# MBC5_1-3.net
KiCad netlist of a schematic drawn in EAGLE
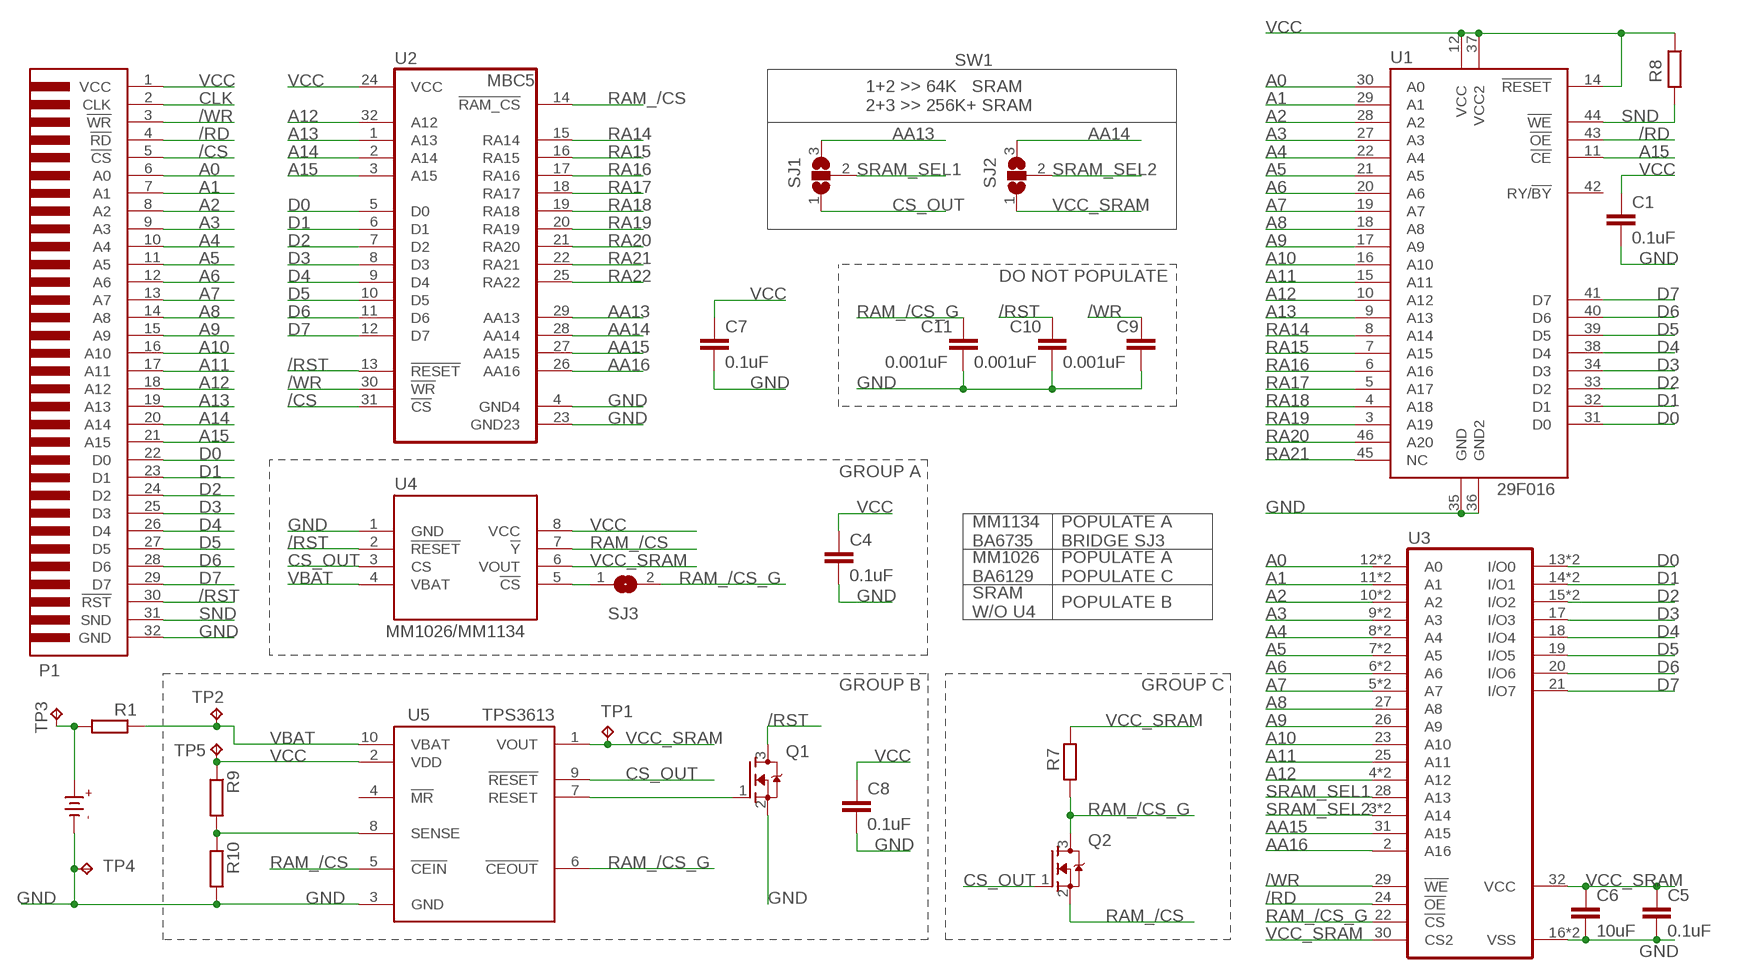
[diagram p0: schematic, sheet 1]

(export (version "E")
  (design (tool "Eeschema 10.0.6"))
  (components
    (comp (ref "B1")
      (value "CR2025")
      (footprint "eagle-import:CR2025")
      (libsource (lib "eagle-import") (part "CR2025"))
    )
    (comp (ref "C1")
      (value "0.1uF")
      (footprint "eagle-import:C0603")
      (libsource (lib "eagle-import") (part "C-EUC0603"))
    )
    (comp (ref "C4")
      (value "0.1uF")
      (footprint "eagle-import:C0603")
      (libsource (lib "eagle-import") (part "C-EUC0603"))
    )
    (comp (ref "C5")
      (value "0.1uF")
      (footprint "eagle-import:C0603")
      (libsource (lib "eagle-import") (part "C-EUC0603"))
    )
    (comp (ref "C6")
      (value "10uF")
      (footprint "eagle-import:C0603")
      (libsource (lib "eagle-import") (part "C-EUC0603"))
    )
    (comp (ref "C7")
      (value "0.1uF")
      (footprint "eagle-import:C0603")
      (libsource (lib "eagle-import") (part "C-EUC0603"))
    )
    (comp (ref "C8")
      (value "0.1uF")
      (footprint "eagle-import:C0603")
      (libsource (lib "eagle-import") (part "C-EUC0603"))
    )
    (comp (ref "C9")
      (value "0.001uF")
      (footprint "eagle-import:C0603")
      (libsource (lib "eagle-import") (part "C-EUC0603"))
    )
    (comp (ref "C10")
      (value "0.001uF")
      (footprint "eagle-import:C0603")
      (libsource (lib "eagle-import") (part "C-EUC0603"))
    )
    (comp (ref "C11")
      (value "0.001uF")
      (footprint "eagle-import:C0603")
      (libsource (lib "eagle-import") (part "C-EUC0603"))
    )
    (comp (ref "P1")
      (value "GBC_CART")
      (footprint "eagle-import:GBC_CART")
      (libsource (lib "eagle-import") (part "GBC_CART"))
    )
    (comp (ref "Q1")
      (value "2N7002")
      (footprint "eagle-import:SOT23")
      (libsource (lib "eagle-import") (part "MOSFET-NREFLOW"))
    )
    (comp (ref "Q2")
      (value "2N7002")
      (footprint "eagle-import:SOT23")
      (libsource (lib "eagle-import") (part "MOSFET-NREFLOW"))
    )
    (comp (ref "R1")
      (value "RR0603")
      (footprint "eagle-import:R0603")
      (libsource (lib "eagle-import") (part "RR0603"))
    )
    (comp (ref "R7")
      (value "RR0603")
      (footprint "eagle-import:R0603")
      (libsource (lib "eagle-import") (part "RR0603"))
    )
    (comp (ref "R8")
      (value "RR0603")
      (footprint "eagle-import:R0603")
      (libsource (lib "eagle-import") (part "RR0603"))
    )
    (comp (ref "R9")
      (value "RR0603")
      (footprint "eagle-import:R0603")
      (libsource (lib "eagle-import") (part "RR0603"))
    )
    (comp (ref "R10")
      (value "RR0603")
      (footprint "eagle-import:R0603")
      (libsource (lib "eagle-import") (part "RR0603"))
    )
    (comp (ref "SJ1")
      (value "SJ2W")
      (footprint "eagle-import:SJ_2")
      (libsource (lib "eagle-import") (part "SJ2W"))
    )
    (comp (ref "SJ2")
      (value "SJ2W")
      (footprint "eagle-import:SJ_2")
      (libsource (lib "eagle-import") (part "SJ2W"))
    )
    (comp (ref "SJ3") (value "SJ") (footprint "eagle-import:SJ") (libsource (lib "eagle-import") (part "SJ")))
    (comp (ref "TP1")
      (value "TPB1,27")
      (footprint "eagle-import:B1,27")
      (libsource (lib "eagle-import") (part "TPB1,27"))
    )
    (comp (ref "TP2")
      (value "TPB1,27")
      (footprint "eagle-import:B1,27")
      (libsource (lib "eagle-import") (part "TPB1,27"))
    )
    (comp (ref "TP3")
      (value "TPB1,27")
      (footprint "eagle-import:B1,27")
      (libsource (lib "eagle-import") (part "TPB1,27"))
    )
    (comp (ref "TP4")
      (value "TPB1,27")
      (footprint "eagle-import:B1,27")
      (libsource (lib "eagle-import") (part "TPB1,27"))
    )
    (comp (ref "TP5")
      (value "TPB1,27")
      (footprint "eagle-import:B1,27")
      (libsource (lib "eagle-import") (part "TPB1,27"))
    )
    (comp (ref "U1")
      (value "29F016")
      (footprint "eagle-import:TSOP-48")
      (libsource (lib "eagle-import") (part "29F016"))
    )
    (comp (ref "U2")
      (value "MBC5")
      (footprint "eagle-import:QFP-32")
      (libsource (lib "eagle-import") (part "MBC5"))
    )
    (comp (ref "U3")
      (value "1008L")
      (footprint "eagle-import:SO32L_L")
      (libsource (lib "eagle-import") (part "1008L"))
    )
    (comp (ref "U4")
      (value "MM1134")
      (footprint "eagle-import:SOIC-8")
      (libsource (lib "eagle-import") (part "MM1134"))
    )
    (comp (ref "U5")
      (value "TPS3613")
      (footprint "eagle-import:MSOP-10")
      (libsource (lib "eagle-import") (part "TPS3613"))
    )
  )
  (nets
    (net (code "1") (name "/A0") (class "Default")
      (node (ref "P1") (pin "6") (pinfunction "A0_6") (pintype "output"))
      (node (ref "U1") (pin "30") (pinfunction "A0_30") (pintype "input"))
      (node (ref "U3") (pin "12") (pinfunction "A0_12") (pintype "input"))
      (node (ref "U3") (pin "L12") (pinfunction "A0_L12") (pintype "input"))
    )
    (net (code "2") (name "/A1") (class "Default")
      (node (ref "P1") (pin "7") (pinfunction "A1_7") (pintype "output"))
      (node (ref "U1") (pin "29") (pinfunction "A1_29") (pintype "input"))
      (node (ref "U3") (pin "11") (pinfunction "A1_11") (pintype "input"))
      (node (ref "U3") (pin "L11") (pinfunction "A1_L11") (pintype "input"))
    )
    (net (code "3") (name "/A2") (class "Default")
      (node (ref "P1") (pin "8") (pinfunction "A2_8") (pintype "output"))
      (node (ref "U1") (pin "28") (pinfunction "A2_28") (pintype "input"))
      (node (ref "U3") (pin "10") (pinfunction "A2_10") (pintype "input"))
      (node (ref "U3") (pin "L10") (pinfunction "A2_L10") (pintype "input"))
    )
    (net (code "4") (name "/A3") (class "Default")
      (node (ref "P1") (pin "9") (pinfunction "A3_9") (pintype "output"))
      (node (ref "U1") (pin "27") (pinfunction "A3_27") (pintype "input"))
      (node (ref "U3") (pin "9") (pinfunction "A3_9") (pintype "input"))
      (node (ref "U3") (pin "L9") (pinfunction "A3_L9") (pintype "input"))
    )
    (net (code "5") (name "/A4") (class "Default")
      (node (ref "P1") (pin "10") (pinfunction "A4_10") (pintype "output"))
      (node (ref "U1") (pin "22") (pinfunction "A4_22") (pintype "input"))
      (node (ref "U3") (pin "8") (pinfunction "A4_8") (pintype "input"))
      (node (ref "U3") (pin "L8") (pinfunction "A4_L8") (pintype "input"))
    )
    (net (code "6") (name "/A5") (class "Default")
      (node (ref "P1") (pin "11") (pinfunction "A5_11") (pintype "output"))
      (node (ref "U1") (pin "21") (pinfunction "A5_21") (pintype "input"))
      (node (ref "U3") (pin "7") (pinfunction "A5_7") (pintype "input"))
      (node (ref "U3") (pin "L7") (pinfunction "A5_L7") (pintype "input"))
    )
    (net (code "7") (name "/A6") (class "Default")
      (node (ref "P1") (pin "12") (pinfunction "A6_12") (pintype "output"))
      (node (ref "U1") (pin "20") (pinfunction "A6_20") (pintype "input"))
      (node (ref "U3") (pin "6") (pinfunction "A6_6") (pintype "input"))
      (node (ref "U3") (pin "L6") (pinfunction "A6_L6") (pintype "input"))
    )
    (net (code "8") (name "/A7") (class "Default")
      (node (ref "P1") (pin "13") (pinfunction "A7_13") (pintype "output"))
      (node (ref "U1") (pin "19") (pinfunction "A7_19") (pintype "input"))
      (node (ref "U3") (pin "5") (pinfunction "A7_5") (pintype "input"))
      (node (ref "U3") (pin "L5") (pinfunction "A7_L5") (pintype "input"))
    )
    (net (code "9") (name "/A8") (class "Default")
      (node (ref "P1") (pin "14") (pinfunction "A8_14") (pintype "output"))
      (node (ref "U1") (pin "18") (pinfunction "A8_18") (pintype "input"))
      (node (ref "U3") (pin "27") (pinfunction "A8_27") (pintype "input"))
    )
    (net (code "10") (name "/A9") (class "Default")
      (node (ref "P1") (pin "15") (pinfunction "A9_15") (pintype "output"))
      (node (ref "U1") (pin "17") (pinfunction "A9_17") (pintype "input"))
      (node (ref "U3") (pin "26") (pinfunction "A9_26") (pintype "input"))
    )
    (net (code "11") (name "/A10") (class "Default")
      (node (ref "P1") (pin "16") (pinfunction "A10_16") (pintype "output"))
      (node (ref "U1") (pin "16") (pinfunction "A10_16") (pintype "input"))
      (node (ref "U3") (pin "23") (pinfunction "A10_23") (pintype "input"))
    )
    (net (code "12") (name "/A11") (class "Default")
      (node (ref "P1") (pin "17") (pinfunction "A11_17") (pintype "output"))
      (node (ref "U1") (pin "15") (pinfunction "A11_15") (pintype "input"))
      (node (ref "U3") (pin "25") (pinfunction "A11_25") (pintype "input"))
    )
    (net (code "13") (name "/A12") (class "Default")
      (node (ref "P1") (pin "18") (pinfunction "A12_18") (pintype "output"))
      (node (ref "U1") (pin "10") (pinfunction "A12_10") (pintype "input"))
      (node (ref "U2") (pin "32") (pinfunction "A12_32") (pintype "input"))
      (node (ref "U3") (pin "4") (pinfunction "A12_4") (pintype "input"))
      (node (ref "U3") (pin "L4") (pinfunction "A12_L4") (pintype "input"))
    )
    (net (code "14") (name "/A13") (class "Default")
      (node (ref "P1") (pin "19") (pinfunction "A13_19") (pintype "output"))
      (node (ref "U1") (pin "9") (pinfunction "A13_9") (pintype "input"))
      (node (ref "U2") (pin "1") (pinfunction "A13_1") (pintype "input"))
    )
    (net (code "15") (name "/A14") (class "Default")
      (node (ref "P1") (pin "20") (pinfunction "A14_20") (pintype "output"))
      (node (ref "U2") (pin "2") (pinfunction "A14_2") (pintype "input"))
    )
    (net (code "16") (name "/A15") (class "Default")
      (node (ref "P1") (pin "21") (pinfunction "A15_21") (pintype "output"))
      (node (ref "U1") (pin "11") (pinfunction "~{CE}_11") (pintype "input"))
      (node (ref "U2") (pin "3") (pinfunction "A15_3") (pintype "input"))
    )
    (net (code "17") (name "/AA13") (class "Default")
      (node (ref "SJ1") (pin "3") (pinfunction "3_3") (pintype "passive"))
      (node (ref "U2") (pin "29") (pinfunction "AA13_29") (pintype "output"))
    )
    (net (code "18") (name "/AA14") (class "Default")
      (node (ref "SJ2") (pin "3") (pinfunction "3_3") (pintype "passive"))
      (node (ref "U2") (pin "28") (pinfunction "AA14_28") (pintype "output"))
    )
    (net (code "19") (name "/AA15") (class "Default")
      (node (ref "U2") (pin "27") (pinfunction "AA15_27") (pintype "output"))
      (node (ref "U3") (pin "31") (pinfunction "A15_31") (pintype "input"))
    )
    (net (code "20") (name "/AA16") (class "Default")
      (node (ref "U2") (pin "26") (pinfunction "AA16_26") (pintype "output"))
      (node (ref "U3") (pin "2") (pinfunction "A16_2") (pintype "input"))
    )
    (net (code "21") (name "/CLK") (class "Default")
      (node (ref "P1") (pin "2") (pinfunction "CLK_2") (pintype "output"))
    )
    (net (code "22") (name "/CS_OUT") (class "Default")
      (node (ref "Q2") (pin "1") (pinfunction "G_1") (pintype "bidirectional"))
      (node (ref "SJ1") (pin "1") (pinfunction "1_1") (pintype "passive"))
      (node (ref "U4") (pin "3") (pinfunction "CS_3") (pintype "output"))
      (node (ref "U5") (pin "9") (pinfunction "~{RESET}_9") (pintype "output"))
    )
    (net (code "23") (name "/D0") (class "Default")
      (node (ref "P1") (pin "22") (pinfunction "D0_22") (pintype "bidirectional"))
      (node (ref "U1") (pin "31") (pinfunction "D0_31") (pintype "bidirectional"))
      (node (ref "U2") (pin "5") (pinfunction "D0_5") (pintype "input"))
      (node (ref "U3") (pin "13") (pinfunction "I/O0_13") (pintype "bidirectional"))
      (node (ref "U3") (pin "L13") (pinfunction "I/O0_L13") (pintype "bidirectional"))
    )
    (net (code "24") (name "/D1") (class "Default")
      (node (ref "P1") (pin "23") (pinfunction "D1_23") (pintype "bidirectional"))
      (node (ref "U1") (pin "32") (pinfunction "D1_32") (pintype "bidirectional"))
      (node (ref "U2") (pin "6") (pinfunction "D1_6") (pintype "input"))
      (node (ref "U3") (pin "14") (pinfunction "I/O1_14") (pintype "bidirectional"))
      (node (ref "U3") (pin "L14") (pinfunction "I/O1_L14") (pintype "bidirectional"))
    )
    (net (code "25") (name "/D2") (class "Default")
      (node (ref "P1") (pin "24") (pinfunction "D2_24") (pintype "bidirectional"))
      (node (ref "U1") (pin "33") (pinfunction "D2_33") (pintype "bidirectional"))
      (node (ref "U2") (pin "7") (pinfunction "D2_7") (pintype "input"))
      (node (ref "U3") (pin "15") (pinfunction "I/O2_15") (pintype "bidirectional"))
      (node (ref "U3") (pin "L15") (pinfunction "I/O2_L15") (pintype "bidirectional"))
    )
    (net (code "26") (name "/D3") (class "Default")
      (node (ref "P1") (pin "25") (pinfunction "D3_25") (pintype "bidirectional"))
      (node (ref "U1") (pin "34") (pinfunction "D3_34") (pintype "bidirectional"))
      (node (ref "U2") (pin "8") (pinfunction "D3_8") (pintype "input"))
      (node (ref "U3") (pin "17") (pinfunction "I/O3_17") (pintype "bidirectional"))
    )
    (net (code "27") (name "/D4") (class "Default")
      (node (ref "P1") (pin "26") (pinfunction "D4_26") (pintype "bidirectional"))
      (node (ref "U1") (pin "38") (pinfunction "D4_38") (pintype "bidirectional"))
      (node (ref "U2") (pin "9") (pinfunction "D4_9") (pintype "input"))
      (node (ref "U3") (pin "18") (pinfunction "I/O4_18") (pintype "bidirectional"))
    )
    (net (code "28") (name "/D5") (class "Default")
      (node (ref "P1") (pin "27") (pinfunction "D5_27") (pintype "bidirectional"))
      (node (ref "U1") (pin "39") (pinfunction "D5_39") (pintype "bidirectional"))
      (node (ref "U2") (pin "10") (pinfunction "D5_10") (pintype "input"))
      (node (ref "U3") (pin "19") (pinfunction "I/O5_19") (pintype "bidirectional"))
    )
    (net (code "29") (name "/D6") (class "Default")
      (node (ref "P1") (pin "28") (pinfunction "D6_28") (pintype "bidirectional"))
      (node (ref "U1") (pin "40") (pinfunction "D6_40") (pintype "bidirectional"))
      (node (ref "U2") (pin "11") (pinfunction "D6_11") (pintype "input"))
      (node (ref "U3") (pin "20") (pinfunction "I/O6_20") (pintype "bidirectional"))
    )
    (net (code "30") (name "/D7") (class "Default")
      (node (ref "P1") (pin "29") (pinfunction "D7_29") (pintype "bidirectional"))
      (node (ref "U1") (pin "41") (pinfunction "D7_41") (pintype "bidirectional"))
      (node (ref "U2") (pin "12") (pinfunction "D7_12") (pintype "input"))
      (node (ref "U3") (pin "21") (pinfunction "I/O7_21") (pintype "bidirectional"))
    )
    (net (code "31") (name "/GND") (class "Default")
      (node (ref "B1") (pin "-") (pinfunction "-_-") (pintype "power_in"))
      (node (ref "C1") (pin "2") (pinfunction "2_2") (pintype "passive"))
      (node (ref "C10") (pin "2") (pinfunction "2_2") (pintype "passive"))
      (node (ref "C11") (pin "2") (pinfunction "2_2") (pintype "passive"))
      (node (ref "C4") (pin "2") (pinfunction "2_2") (pintype "passive"))
      (node (ref "C5") (pin "2") (pinfunction "2_2") (pintype "passive"))
      (node (ref "C6") (pin "2") (pinfunction "2_2") (pintype "passive"))
      (node (ref "C7") (pin "2") (pinfunction "2_2") (pintype "passive"))
      (node (ref "C8") (pin "2") (pinfunction "2_2") (pintype "passive"))
      (node (ref "C9") (pin "2") (pinfunction "2_2") (pintype "passive"))
      (node (ref "P1") (pin "32") (pinfunction "GND_32") (pintype "power_in"))
      (node (ref "Q1") (pin "2") (pinfunction "S_2") (pintype "bidirectional"))
      (node (ref "R10") (pin "2") (pinfunction "2_2") (pintype "passive"))
      (node (ref "TP4") (pin "TP") (pinfunction "TP_TP") (pintype "input"))
      (node (ref "U1") (pin "35") (pinfunction "GND_35") (pintype "power_in"))
      (node (ref "U1") (pin "36") (pinfunction "GND2_36") (pintype "power_in"))
      (node (ref "U2") (pin "23") (pinfunction "GND23_23") (pintype "power_in"))
      (node (ref "U2") (pin "4") (pinfunction "GND4_4") (pintype "power_in"))
      (node (ref "U3") (pin "16") (pinfunction "VSS_16") (pintype "power_in"))
      (node (ref "U3") (pin "L16") (pinfunction "VSS_L16") (pintype "power_in"))
      (node (ref "U4") (pin "1") (pinfunction "GND_1") (pintype "power_in"))
      (node (ref "U5") (pin "3") (pinfunction "GND_3") (pintype "power_in"))
    )
    (net (code "32") (name "/RA14") (class "Default")
      (node (ref "U1") (pin "8") (pinfunction "A14_8") (pintype "input"))
      (node (ref "U2") (pin "15") (pinfunction "RA14_15") (pintype "output"))
    )
    (net (code "33") (name "/RA15") (class "Default")
      (node (ref "U1") (pin "7") (pinfunction "A15_7") (pintype "input"))
      (node (ref "U2") (pin "16") (pinfunction "RA15_16") (pintype "output"))
    )
    (net (code "34") (name "/RA16") (class "Default")
      (node (ref "U1") (pin "6") (pinfunction "A16_6") (pintype "input"))
      (node (ref "U2") (pin "17") (pinfunction "RA16_17") (pintype "output"))
    )
    (net (code "35") (name "/RA17") (class "Default")
      (node (ref "U1") (pin "5") (pinfunction "A17_5") (pintype "input"))
      (node (ref "U2") (pin "18") (pinfunction "RA17_18") (pintype "output"))
    )
    (net (code "36") (name "/RA18") (class "Default")
      (node (ref "U1") (pin "4") (pinfunction "A18_4") (pintype "input"))
      (node (ref "U2") (pin "19") (pinfunction "RA18_19") (pintype "output"))
    )
    (net (code "37") (name "/RA19") (class "Default")
      (node (ref "U1") (pin "3") (pinfunction "A19_3") (pintype "input"))
      (node (ref "U2") (pin "20") (pinfunction "RA19_20") (pintype "output"))
    )
    (net (code "38") (name "/RA20") (class "Default")
      (node (ref "U1") (pin "46") (pinfunction "A20_46") (pintype "input"))
      (node (ref "U2") (pin "21") (pinfunction "RA20_21") (pintype "output"))
    )
    (net (code "39") (name "/RA21") (class "Default")
      (node (ref "U1") (pin "45") (pinfunction "NC_45") (pintype "input"))
      (node (ref "U2") (pin "22") (pinfunction "RA21_22") (pintype "output"))
    )
    (net (code "40") (name "/RA22") (class "Default")
      (node (ref "U2") (pin "25") (pinfunction "RA22_25") (pintype "output"))
    )
    (net (code "41") (name "/RAM_{slash}CS") (class "Default")
      (node (ref "Q2") (pin "2") (pinfunction "S_2") (pintype "bidirectional"))
      (node (ref "U2") (pin "14") (pinfunction "~{RAM_CS}_14") (pintype "output"))
      (node (ref "U4") (pin "7") (pinfunction "~{Y}_7") (pintype "input"))
      (node (ref "U5") (pin "5") (pinfunction "~{CEIN}_5") (pintype "input"))
    )
    (net (code "42") (name "/RAM_{slash}CS_G") (class "Default")
      (node (ref "C11") (pin "1") (pinfunction "1_1") (pintype "passive"))
      (node (ref "Q2") (pin "3") (pinfunction "D_3") (pintype "bidirectional"))
      (node (ref "R7") (pin "1") (pinfunction "1_1") (pintype "passive"))
      (node (ref "SJ3") (pin "2") (pinfunction "2_2") (pintype "passive"))
      (node (ref "U3") (pin "22") (pinfunction "~{CS}_22") (pintype "input"))
      (node (ref "U5") (pin "6") (pinfunction "~{CEOUT}_6") (pintype "output"))
    )
    (net (code "43") (name "/SND") (class "Default")
      (node (ref "P1") (pin "31") (pinfunction "SND_31") (pintype "bidirectional"))
      (node (ref "R8") (pin "2") (pinfunction "2_2") (pintype "passive"))
      (node (ref "U1") (pin "44") (pinfunction "~{WE}_44") (pintype "input"))
    )
    (net (code "44") (name "/SRAM_SEL1") (class "Default")
      (node (ref "SJ1") (pin "2") (pinfunction "2_2") (pintype "passive"))
      (node (ref "U3") (pin "28") (pinfunction "A13_28") (pintype "input"))
    )
    (net (code "45") (name "/SRAM_SEL2") (class "Default")
      (node (ref "SJ2") (pin "2") (pinfunction "2_2") (pintype "passive"))
      (node (ref "U3") (pin "3") (pinfunction "A14_3") (pintype "input"))
      (node (ref "U3") (pin "L3") (pinfunction "A14_L3") (pintype "input"))
    )
    (net (code "46") (name "/VBAT") (class "Default")
      (node (ref "R1") (pin "1") (pinfunction "1_1") (pintype "passive"))
      (node (ref "TP2") (pin "TP") (pinfunction "TP_TP") (pintype "input"))
      (node (ref "U4") (pin "4") (pinfunction "VBAT_4") (pintype "power_in"))
      (node (ref "U5") (pin "10") (pinfunction "VBAT_10") (pintype "power_in"))
    )
    (net (code "47") (name "/VCC") (class "Default")
      (node (ref "C1") (pin "1") (pinfunction "1_1") (pintype "passive"))
      (node (ref "C4") (pin "1") (pinfunction "1_1") (pintype "passive"))
      (node (ref "C7") (pin "1") (pinfunction "1_1") (pintype "passive"))
      (node (ref "C8") (pin "1") (pinfunction "1_1") (pintype "passive"))
      (node (ref "P1") (pin "1") (pinfunction "VCC_1") (pintype "power_in"))
      (node (ref "R8") (pin "1") (pinfunction "1_1") (pintype "passive"))
      (node (ref "R9") (pin "1") (pinfunction "1_1") (pintype "passive"))
      (node (ref "TP5") (pin "TP") (pinfunction "TP_TP") (pintype "input"))
      (node (ref "U1") (pin "12") (pinfunction "VCC_12") (pintype "power_in"))
      (node (ref "U1") (pin "14") (pinfunction "~{RESET}_14") (pintype "input"))
      (node (ref "U1") (pin "37") (pinfunction "VCC2_37") (pintype "power_in"))
      (node (ref "U2") (pin "24") (pinfunction "VCC_24") (pintype "power_in"))
      (node (ref "U4") (pin "8") (pinfunction "VCC_8") (pintype "power_in"))
      (node (ref "U5") (pin "2") (pinfunction "VDD_2") (pintype "power_in"))
    )
    (net (code "48") (name "/VCC_SRAM") (class "Default")
      (node (ref "C5") (pin "1") (pinfunction "1_1") (pintype "passive"))
      (node (ref "C6") (pin "1") (pinfunction "1_1") (pintype "passive"))
      (node (ref "R7") (pin "2") (pinfunction "2_2") (pintype "passive"))
      (node (ref "SJ2") (pin "1") (pinfunction "1_1") (pintype "passive"))
      (node (ref "TP1") (pin "TP") (pinfunction "TP_TP") (pintype "input"))
      (node (ref "U3") (pin "30") (pinfunction "CS2_30") (pintype "input"))
      (node (ref "U3") (pin "32") (pinfunction "VCC_32") (pintype "power_in"))
      (node (ref "U4") (pin "6") (pinfunction "VOUT_6") (pintype "power_in"))
      (node (ref "U5") (pin "1") (pinfunction "VOUT_1") (pintype "power_in"))
    )
    (net (code "49") (name "/{slash}CS") (class "Default")
      (node (ref "P1") (pin "5") (pinfunction "~{CS}_5") (pintype "output"))
      (node (ref "U2") (pin "31") (pinfunction "~{CS}_31") (pintype "input"))
    )
    (net (code "50") (name "/{slash}RD") (class "Default")
      (node (ref "P1") (pin "4") (pinfunction "~{RD}_4") (pintype "output"))
      (node (ref "U1") (pin "43") (pinfunction "~{OE}_43") (pintype "input"))
      (node (ref "U3") (pin "24") (pinfunction "~{OE}_24") (pintype "input"))
    )
    (net (code "51") (name "/{slash}RST") (class "Default")
      (node (ref "C10") (pin "1") (pinfunction "1_1") (pintype "passive"))
      (node (ref "P1") (pin "30") (pinfunction "~{RST}_30") (pintype "bidirectional"))
      (node (ref "Q1") (pin "3") (pinfunction "D_3") (pintype "bidirectional"))
      (node (ref "U2") (pin "13") (pinfunction "~{RESET}_13") (pintype "input"))
      (node (ref "U4") (pin "2") (pinfunction "~{RESET}_2") (pintype "input"))
    )
    (net (code "52") (name "/{slash}WR") (class "Default")
      (node (ref "C9") (pin "1") (pinfunction "1_1") (pintype "passive"))
      (node (ref "P1") (pin "3") (pinfunction "~{WR}_3") (pintype "output"))
      (node (ref "U2") (pin "30") (pinfunction "~{WR}_30") (pintype "input"))
      (node (ref "U3") (pin "29") (pinfunction "~{WE}_29") (pintype "input"))
    )
    (net (code "53") (name "Net-(B1-Pad+)") (class "Default")
      (node (ref "B1") (pin "+") (pinfunction "+_+") (pintype "power_in"))
      (node (ref "R1") (pin "2") (pinfunction "2_2") (pintype "passive"))
      (node (ref "TP3") (pin "TP") (pinfunction "TP_TP") (pintype "input"))
    )
    (net (code "54") (name "Net-(Q1-G)") (class "Default")
      (node (ref "Q1") (pin "1") (pinfunction "G_1") (pintype "bidirectional"))
      (node (ref "U5") (pin "7") (pinfunction "RESET_7") (pintype "output"))
    )
    (net (code "55") (name "Net-(U4-~{CS})") (class "Default")
      (node (ref "SJ3") (pin "1") (pinfunction "1_1") (pintype "passive"))
      (node (ref "U4") (pin "5") (pinfunction "~{CS}_5") (pintype "output"))
    )
    (net (code "56") (name "Net-(U5-SENSE)") (class "Default")
      (node (ref "R10") (pin "1") (pinfunction "1_1") (pintype "passive"))
      (node (ref "R9") (pin "2") (pinfunction "2_2") (pintype "passive"))
      (node (ref "U5") (pin "8") (pinfunction "SENSE_8") (pintype "input"))
    )
    (net (code "57") (name "unconnected-(U1-RY{slash}~{BY}-Pad42)") (class "Default")
      (node (ref "U1") (pin "42") (pinfunction "RY/~{BY}_42") (pintype "output"))
    )
    (net (code "58") (name "unconnected-(U5-~{MR}-Pad4)") (class "Default")
      (node (ref "U5") (pin "4") (pinfunction "~{MR}_4") (pintype "input"))
    )
  )
)
